# Meas_Board.net
KiCad netlist of a schematic drawn in Altium Designer
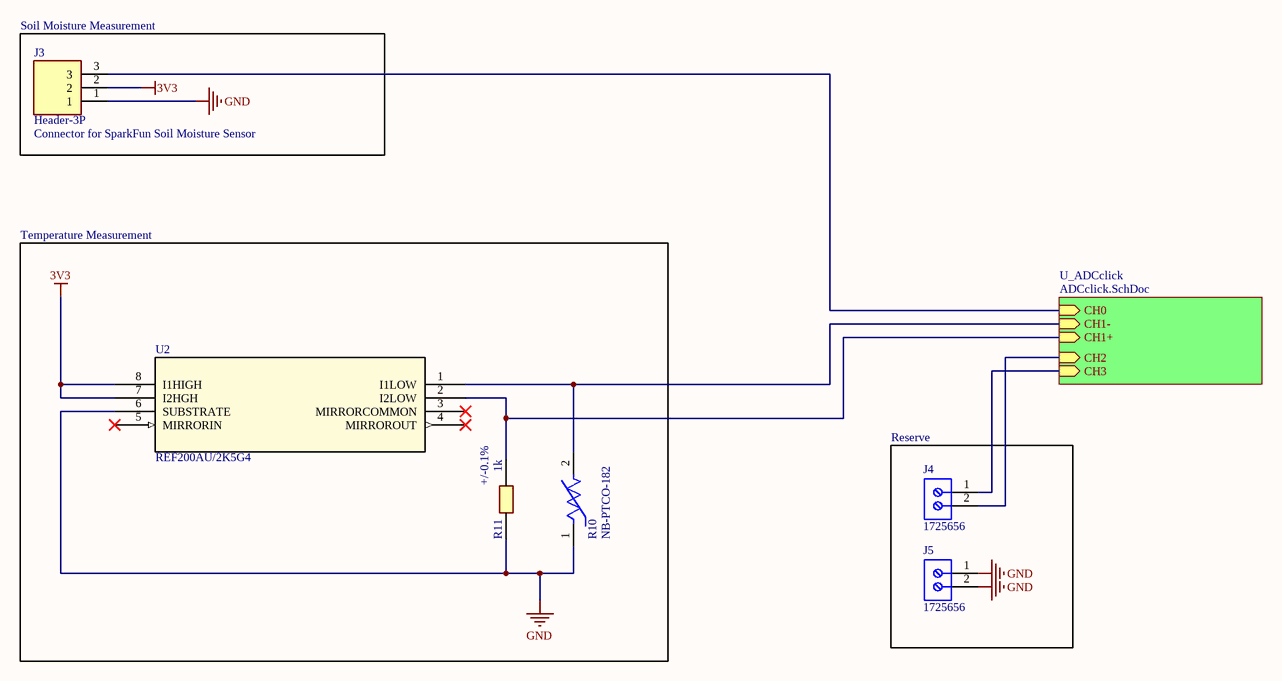
[diagram p0: Meas_Board.SchDoc]

(export (version "E")
  (design (tool "Eeschema 10.0.6"))
  (components
    (comp (ref "J3")
      (value "Header-3P")
      (footprint "HDRV3W64P254_1X3_762X241X838P")
      (description "Connector")
      (fields
        (field (name "MANUFACTURER_PART_NUMBER") "TSW-103-07-S-S-LL")
        (field (name "MOUSER PART NUMBER") "200-TSW10307SSLL")
      )
      (libsource (lib "Integrated_Library1") (part "Header-3P"))
    )
    (comp (ref "J4")
      (value "1725656")
      (footprint "PHOE-1725656-2")
      (description "Male Header, Pitch 2.54 mm, 1 x 2 Position, Height 9 mm, Tail Length 3.5 mm")
      (fields (field (name "MANUFACTURER") "Phoenix Contact"))
      (libsource (lib "Altium Content Vault") (part "CN-1P-F-TB2"))
    )
    (comp (ref "J5")
      (value "1725656")
      (footprint "PHOE-1725656-2")
      (description "Male Header, Pitch 2.54 mm, 1 x 2 Position, Height 9 mm, Tail Length 3.5 mm")
      (fields (field (name "MANUFACTURER") "Phoenix Contact"))
      (libsource (lib "Altium Content Vault") (part "CN-1P-F-TB2"))
    )
    (comp (ref "R10")
      (value "NB-PTCO-182")
      (footprint "FP-PTFF-MFG")
      (description "NB-PTCO-182 Pt1000, 2.0X4.0, Class B, Ptff102B1A0")
      (libsource (lib "Altium Content Vault") (part "3b148a6ebabc5fb4d708a66c052d352"))
    )
    (comp (ref "R11")
      (value "1k")
      (footprint "IMP-0805")
      (description "Resistor")
      (fields
        (field (name "TOLERANCE") "+/-0.1%")
        (field (name "POWER") "125 mW")
        (field (name "Comment") "Res_generic")
      )
      (libsource (lib "Integrated_Library1") (part "Res_generic"))
    )
    (comp (ref "U2")
      (value "REF200AU/2K5G4")
      (footprint "D8_TEX")
      (description "Description")
      (fields (field (name "COPYRIGHT") "Copyright (C) 2026 Ultra Librarian. All rights reserved."))
      (libsource (lib "REF200AU2K5G4") (part "REF200AU2K5G4"))
    )
  )
  (nets
    (net (code "1") (name "/CH0") (class "Default")
      (node (ref "J3") (pin "3") (pinfunction "3_3") (pintype "passive"))
    )
    (net (code "2") (name "/CH1+") (class "Default")
      (node (ref "R11") (pin "2") (pinfunction "2_2") (pintype "passive"))
      (node (ref "U2") (pin "2") (pinfunction "I2LOW_2") (pintype "passive"))
    )
    (net (code "3") (name "/CH1-") (class "Default")
      (node (ref "R10") (pin "2") (pinfunction "2_2") (pintype "passive"))
      (node (ref "U2") (pin "1") (pinfunction "I1LOW_1") (pintype "passive"))
    )
    (net (code "4") (name "/CH2") (class "Default")
      (node (ref "J4") (pin "2") (pinfunction "2_2") (pintype "passive"))
    )
    (net (code "5") (name "/CH3") (class "Default")
      (node (ref "J4") (pin "1") (pinfunction "1_1") (pintype "passive"))
    )
    (net (code "6") (name "3V3") (class "Default")
      (node (ref "J3") (pin "2") (pinfunction "2_2") (pintype "passive"))
      (node (ref "U2") (pin "7") (pinfunction "I2HGH_7") (pintype "passive"))
      (node (ref "U2") (pin "8") (pinfunction "I1HIGH_8") (pintype "passive"))
    )
    (net (code "7") (name "GND") (class "Default")
      (node (ref "J3") (pin "1") (pinfunction "1_1") (pintype "passive"))
      (node (ref "J5") (pin "1") (pinfunction "1_1") (pintype "passive"))
      (node (ref "J5") (pin "2") (pinfunction "2_2") (pintype "passive"))
      (node (ref "R10") (pin "1") (pinfunction "1_1") (pintype "passive"))
      (node (ref "R11") (pin "1") (pinfunction "1_1") (pintype "passive"))
      (node (ref "U2") (pin "6") (pinfunction "SUBSTRATE_6") (pintype "passive"))
    )
    (net (code "8") (name "unconnected-(U2-MIRRORCOMMON-Pad3)") (class "Default")
      (node (ref "U2") (pin "3") (pinfunction "MIRRORCOMMON_3") (pintype "passive+no_connect"))
    )
    (net (code "9") (name "unconnected-(U2-MIRRORIN-Pad5)") (class "Default")
      (node (ref "U2") (pin "5") (pinfunction "MIRRORIN_5") (pintype "input+no_connect"))
    )
    (net (code "10") (name "unconnected-(U2-MIRROROUT-Pad4)") (class "Default")
      (node (ref "U2") (pin "4") (pinfunction "MIRROROUT_4") (pintype "output+no_connect"))
    )
  )
)
